# ifcBoard.net
KiCad netlist of a schematic drawn in EAGLE
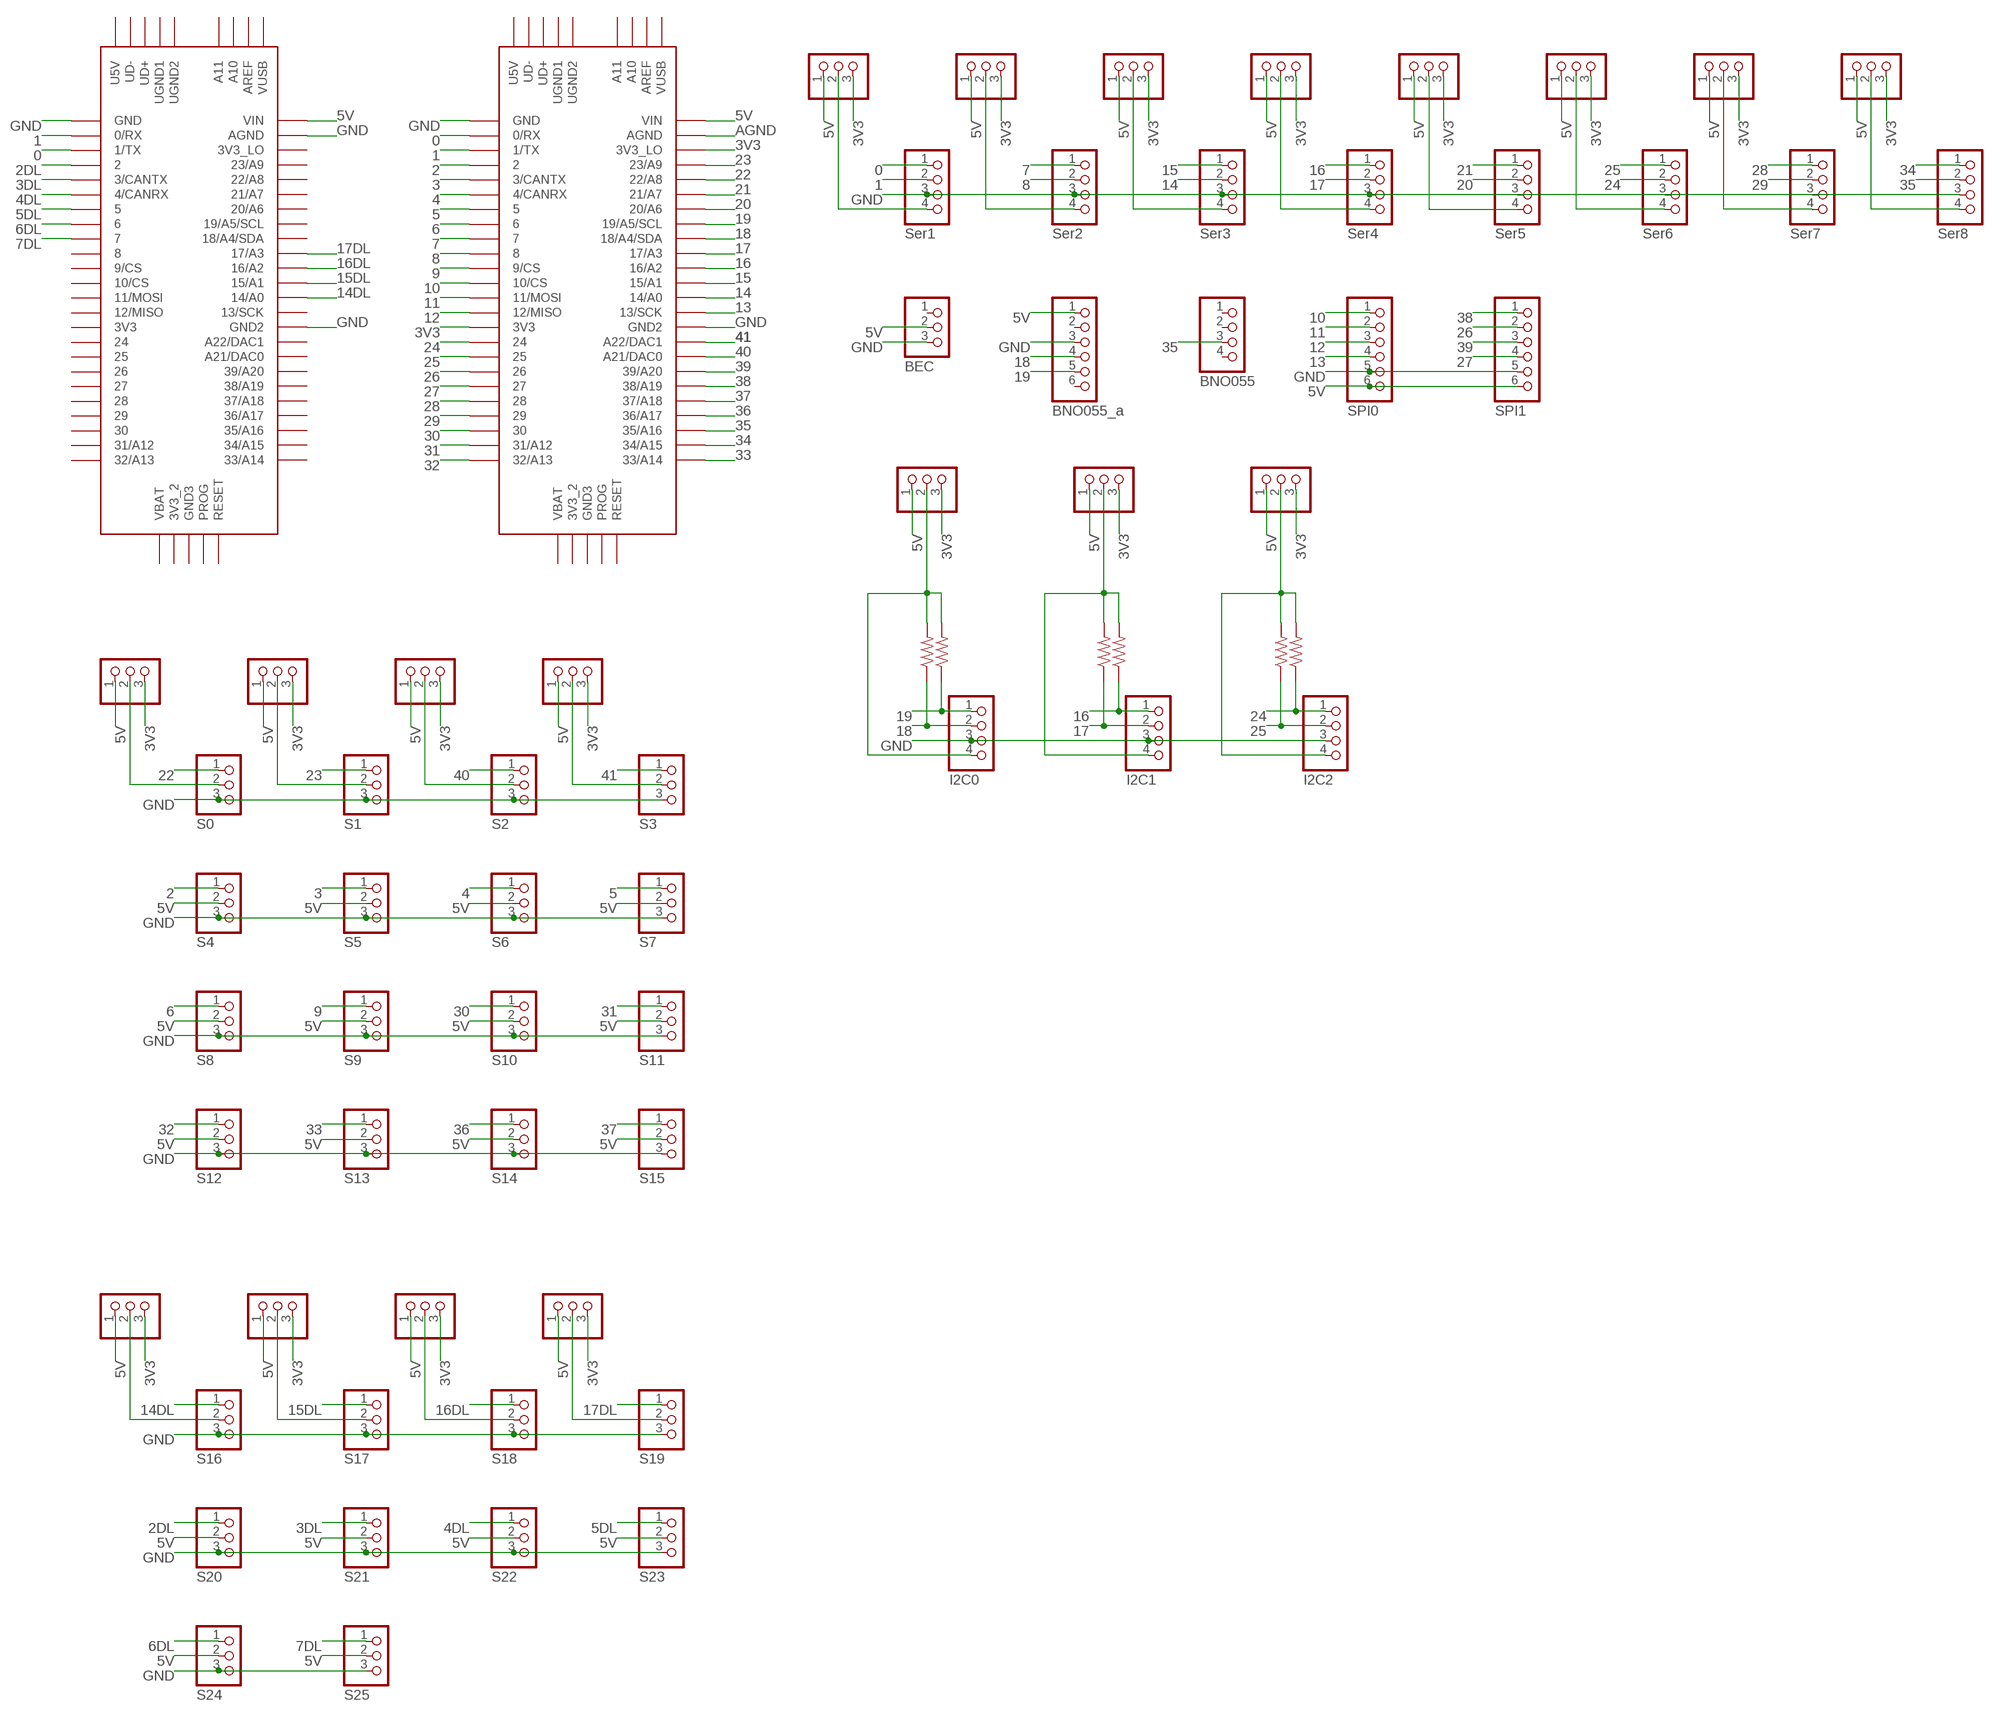
[diagram p0: schematic, sheet 1]

(export (version "E")
  (design (tool "Eeschema 10.0.6"))
  (components
    (comp (ref "JP1")
      (value "BEC")
      (footprint "eagle-import:1X03")
      (libsource (lib "eagle-import") (part "PINHD-1X3"))
    )
    (comp (ref "JP2")
      (value "S0")
      (footprint "eagle-import:1X03")
      (libsource (lib "eagle-import") (part "PINHD-1X3"))
    )
    (comp (ref "JP3")
      (value "S1")
      (footprint "eagle-import:1X03")
      (libsource (lib "eagle-import") (part "PINHD-1X3"))
    )
    (comp (ref "JP4")
      (value "S2")
      (footprint "eagle-import:1X03")
      (libsource (lib "eagle-import") (part "PINHD-1X3"))
    )
    (comp (ref "JP5")
      (value "S3")
      (footprint "eagle-import:1X03")
      (libsource (lib "eagle-import") (part "PINHD-1X3"))
    )
    (comp (ref "JP6")
      (value "S4")
      (footprint "eagle-import:1X03")
      (libsource (lib "eagle-import") (part "PINHD-1X3"))
    )
    (comp (ref "JP7")
      (value "S5")
      (footprint "eagle-import:1X03")
      (libsource (lib "eagle-import") (part "PINHD-1X3"))
    )
    (comp (ref "JP8")
      (value "S6")
      (footprint "eagle-import:1X03")
      (libsource (lib "eagle-import") (part "PINHD-1X3"))
    )
    (comp (ref "JP9")
      (value "S7")
      (footprint "eagle-import:1X03")
      (libsource (lib "eagle-import") (part "PINHD-1X3"))
    )
    (comp (ref "JP10")
      (value "S8")
      (footprint "eagle-import:1X03")
      (libsource (lib "eagle-import") (part "PINHD-1X3"))
    )
    (comp (ref "JP11")
      (value "S9")
      (footprint "eagle-import:1X03")
      (libsource (lib "eagle-import") (part "PINHD-1X3"))
    )
    (comp (ref "JP12")
      (value "S10")
      (footprint "eagle-import:1X03")
      (libsource (lib "eagle-import") (part "PINHD-1X3"))
    )
    (comp (ref "JP13")
      (value "S11")
      (footprint "eagle-import:1X03")
      (libsource (lib "eagle-import") (part "PINHD-1X3"))
    )
    (comp (ref "JP14")
      (value "S12")
      (footprint "eagle-import:1X03")
      (libsource (lib "eagle-import") (part "PINHD-1X3"))
    )
    (comp (ref "JP15")
      (value "S13")
      (footprint "eagle-import:1X03")
      (libsource (lib "eagle-import") (part "PINHD-1X3"))
    )
    (comp (ref "JP16")
      (value "S14")
      (footprint "eagle-import:1X03")
      (libsource (lib "eagle-import") (part "PINHD-1X3"))
    )
    (comp (ref "JP17")
      (value "S15")
      (footprint "eagle-import:1X03")
      (libsource (lib "eagle-import") (part "PINHD-1X3"))
    )
    (comp (ref "JP18")
      (value "Ser6")
      (footprint "eagle-import:1X04")
      (libsource (lib "eagle-import") (part "PINHD-1X4"))
    )
    (comp (ref "JP19")
      (value "S0")
      (footprint "eagle-import:1X03")
      (libsource (lib "eagle-import") (part "PINHD-1X3"))
    )
    (comp (ref "JP20")
      (value "S0")
      (footprint "eagle-import:1X03")
      (libsource (lib "eagle-import") (part "PINHD-1X3"))
    )
    (comp (ref "JP21")
      (value "Ser7")
      (footprint "eagle-import:1X04")
      (libsource (lib "eagle-import") (part "PINHD-1X4"))
    )
    (comp (ref "JP22")
      (value "I2C0")
      (footprint "eagle-import:1X04")
      (libsource (lib "eagle-import") (part "PINHD-1X4"))
    )
    (comp (ref "JP23")
      (value "Ser1")
      (footprint "eagle-import:1X04")
      (libsource (lib "eagle-import") (part "PINHD-1X4"))
    )
    (comp (ref "JP24")
      (value "Ser2")
      (footprint "eagle-import:1X04")
      (libsource (lib "eagle-import") (part "PINHD-1X4"))
    )
    (comp (ref "JP25")
      (value "Ser3")
      (footprint "eagle-import:1X04")
      (libsource (lib "eagle-import") (part "PINHD-1X4"))
    )
    (comp (ref "JP26")
      (value "Ser4")
      (footprint "eagle-import:1X04")
      (libsource (lib "eagle-import") (part "PINHD-1X4"))
    )
    (comp (ref "JP27")
      (value "Ser5")
      (footprint "eagle-import:1X04")
      (libsource (lib "eagle-import") (part "PINHD-1X4"))
    )
    (comp (ref "JP28")
      (value "I2C1")
      (footprint "eagle-import:1X04")
      (libsource (lib "eagle-import") (part "PINHD-1X4"))
    )
    (comp (ref "JP29")
      (value "I2C2")
      (footprint "eagle-import:1X04")
      (libsource (lib "eagle-import") (part "PINHD-1X4"))
    )
    (comp (ref "JP30")
      (value "Ser8")
      (footprint "eagle-import:1X04")
      (libsource (lib "eagle-import") (part "PINHD-1X4"))
    )
    (comp (ref "JP31")
      (value "SPI0")
      (footprint "eagle-import:1X06")
      (libsource (lib "eagle-import") (part "PINHD-1X6"))
    )
    (comp (ref "JP32")
      (value "SPI1")
      (footprint "eagle-import:1X06")
      (libsource (lib "eagle-import") (part "PINHD-1X6"))
    )
    (comp (ref "JP33")
      (value "BNO055_a")
      (footprint "eagle-import:1X06")
      (libsource (lib "eagle-import") (part "PINHD-1X6"))
    )
    (comp (ref "JP34")
      (value "BNO055")
      (footprint "eagle-import:1X04")
      (libsource (lib "eagle-import") (part "PINHD-1X4"))
    )
    (comp (ref "JP35")
      (value "S0")
      (footprint "eagle-import:1X03")
      (libsource (lib "eagle-import") (part "PINHD-1X3"))
    )
    (comp (ref "JP36")
      (value "S0")
      (footprint "eagle-import:1X03")
      (libsource (lib "eagle-import") (part "PINHD-1X3"))
    )
    (comp (ref "JP37")
      (value "S0")
      (footprint "eagle-import:1X03")
      (libsource (lib "eagle-import") (part "PINHD-1X3"))
    )
    (comp (ref "JP38")
      (value "S0")
      (footprint "eagle-import:1X03")
      (libsource (lib "eagle-import") (part "PINHD-1X3"))
    )
    (comp (ref "JP39")
      (value "S0")
      (footprint "eagle-import:1X03")
      (libsource (lib "eagle-import") (part "PINHD-1X3"))
    )
    (comp (ref "JP40")
      (value "S0")
      (footprint "eagle-import:1X03")
      (libsource (lib "eagle-import") (part "PINHD-1X3"))
    )
    (comp (ref "JP41")
      (value "S0")
      (footprint "eagle-import:1X03")
      (libsource (lib "eagle-import") (part "PINHD-1X3"))
    )
    (comp (ref "JP42")
      (value "S0")
      (footprint "eagle-import:1X03")
      (libsource (lib "eagle-import") (part "PINHD-1X3"))
    )
    (comp (ref "JP43")
      (value "S0")
      (footprint "eagle-import:1X03")
      (libsource (lib "eagle-import") (part "PINHD-1X3"))
    )
    (comp (ref "JP44")
      (value "S0")
      (footprint "eagle-import:1X03")
      (libsource (lib "eagle-import") (part "PINHD-1X3"))
    )
    (comp (ref "JP45")
      (value "S0")
      (footprint "eagle-import:1X03")
      (libsource (lib "eagle-import") (part "PINHD-1X3"))
    )
    (comp (ref "JP46")
      (value "S0")
      (footprint "eagle-import:1X03")
      (libsource (lib "eagle-import") (part "PINHD-1X3"))
    )
    (comp (ref "JP47")
      (value "S0")
      (footprint "eagle-import:1X03")
      (libsource (lib "eagle-import") (part "PINHD-1X3"))
    )
    (comp (ref "JP58")
      (value "S16")
      (footprint "eagle-import:1X03")
      (libsource (lib "eagle-import") (part "PINHD-1X3"))
    )
    (comp (ref "JP59")
      (value "S17")
      (footprint "eagle-import:1X03")
      (libsource (lib "eagle-import") (part "PINHD-1X3"))
    )
    (comp (ref "JP60")
      (value "S18")
      (footprint "eagle-import:1X03")
      (libsource (lib "eagle-import") (part "PINHD-1X3"))
    )
    (comp (ref "JP61")
      (value "S19")
      (footprint "eagle-import:1X03")
      (libsource (lib "eagle-import") (part "PINHD-1X3"))
    )
    (comp (ref "JP62")
      (value "S23")
      (footprint "eagle-import:1X03")
      (libsource (lib "eagle-import") (part "PINHD-1X3"))
    )
    (comp (ref "JP63")
      (value "S22")
      (footprint "eagle-import:1X03")
      (libsource (lib "eagle-import") (part "PINHD-1X3"))
    )
    (comp (ref "JP64")
      (value "S0")
      (footprint "eagle-import:1X03")
      (libsource (lib "eagle-import") (part "PINHD-1X3"))
    )
    (comp (ref "JP65")
      (value "S0")
      (footprint "eagle-import:1X03")
      (libsource (lib "eagle-import") (part "PINHD-1X3"))
    )
    (comp (ref "JP66")
      (value "S0")
      (footprint "eagle-import:1X03")
      (libsource (lib "eagle-import") (part "PINHD-1X3"))
    )
    (comp (ref "JP67")
      (value "S0")
      (footprint "eagle-import:1X03")
      (libsource (lib "eagle-import") (part "PINHD-1X3"))
    )
    (comp (ref "JP68")
      (value "S21")
      (footprint "eagle-import:1X03")
      (libsource (lib "eagle-import") (part "PINHD-1X3"))
    )
    (comp (ref "JP69")
      (value "S20")
      (footprint "eagle-import:1X03")
      (libsource (lib "eagle-import") (part "PINHD-1X3"))
    )
    (comp (ref "JP70")
      (value "S24")
      (footprint "eagle-import:1X03")
      (libsource (lib "eagle-import") (part "PINHD-1X3"))
    )
    (comp (ref "JP71")
      (value "S25")
      (footprint "eagle-import:1X03")
      (libsource (lib "eagle-import") (part "PINHD-1X3"))
    )
    (comp (ref "R2")
      (value "R-US_0207/12")
      (footprint "eagle-import:0207_12")
      (libsource (lib "eagle-import") (part "R-US_0207/12"))
    )
    (comp (ref "R3")
      (value "R-US_0207/12")
      (footprint "eagle-import:0207_12")
      (libsource (lib "eagle-import") (part "R-US_0207/12"))
    )
    (comp (ref "R4")
      (value "R-US_0207/12")
      (footprint "eagle-import:0207_12")
      (libsource (lib "eagle-import") (part "R-US_0207/12"))
    )
    (comp (ref "R5")
      (value "R-US_0207/12")
      (footprint "eagle-import:0207_12")
      (libsource (lib "eagle-import") (part "R-US_0207/12"))
    )
    (comp (ref "R6")
      (value "R-US_0207/12")
      (footprint "eagle-import:0207_12")
      (libsource (lib "eagle-import") (part "R-US_0207/12"))
    )
    (comp (ref "R7")
      (value "R-US_0207/12")
      (footprint "eagle-import:0207_12")
      (libsource (lib "eagle-import") (part "R-US_0207/12"))
    )
    (comp (ref "U$1")
      (value "TEENSY_3.5/3.6")
      (footprint "eagle-import:TEENSY_3.5_3.6")
      (libsource (lib "eagle-import") (part "TEENSY_3.5/3.6"))
    )
    (comp (ref "U$2")
      (value "TEENSY_3.5/3.6")
      (footprint "eagle-import:TEENSY_3.5_3.6")
      (libsource (lib "eagle-import") (part "TEENSY_3.5/3.6"))
    )
  )
  (nets
    (net (code "1") (name "/0") (class "Default")
      (node (ref "JP23") (pin "1") (pinfunction "1_1") (pintype "passive"))
      (node (ref "U$1") (pin "0/RX") (pinfunction "0/RX_0/RX") (pintype "bidirectional"))
      (node (ref "U$2") (pin "1/TX") (pinfunction "1/TX_1/TX") (pintype "bidirectional"))
    )
    (net (code "2") (name "/1") (class "Default")
      (node (ref "JP23") (pin "2") (pinfunction "2_2") (pintype "passive"))
      (node (ref "U$1") (pin "1/TX") (pinfunction "1/TX_1/TX") (pintype "bidirectional"))
      (node (ref "U$2") (pin "0/RX") (pinfunction "0/RX_0/RX") (pintype "bidirectional"))
    )
    (net (code "3") (name "/2") (class "Default")
      (node (ref "JP6") (pin "1") (pinfunction "1_1") (pintype "passive"))
      (node (ref "U$1") (pin "2") (pinfunction "2_2") (pintype "bidirectional"))
    )
    (net (code "4") (name "/2DL") (class "Default")
      (node (ref "JP69") (pin "1") (pinfunction "1_1") (pintype "passive"))
      (node (ref "U$2") (pin "2") (pinfunction "2_2") (pintype "bidirectional"))
    )
    (net (code "5") (name "/3") (class "Default")
      (node (ref "JP7") (pin "1") (pinfunction "1_1") (pintype "passive"))
      (node (ref "U$1") (pin "3/CANTX") (pinfunction "3/CANTX_3/CANTX") (pintype "bidirectional"))
    )
    (net (code "6") (name "/3DL") (class "Default")
      (node (ref "JP68") (pin "1") (pinfunction "1_1") (pintype "passive"))
      (node (ref "U$2") (pin "3/CANTX") (pinfunction "3/CANTX_3/CANTX") (pintype "bidirectional"))
    )
    (net (code "7") (name "/3V3") (class "Default")
      (node (ref "JP19") (pin "3") (pinfunction "3_3") (pintype "passive"))
      (node (ref "JP20") (pin "3") (pinfunction "3_3") (pintype "passive"))
      (node (ref "JP35") (pin "3") (pinfunction "3_3") (pintype "passive"))
      (node (ref "JP36") (pin "3") (pinfunction "3_3") (pintype "passive"))
      (node (ref "JP37") (pin "3") (pinfunction "3_3") (pintype "passive"))
      (node (ref "JP38") (pin "3") (pinfunction "3_3") (pintype "passive"))
      (node (ref "JP39") (pin "3") (pinfunction "3_3") (pintype "passive"))
      (node (ref "JP40") (pin "3") (pinfunction "3_3") (pintype "passive"))
      (node (ref "JP41") (pin "3") (pinfunction "3_3") (pintype "passive"))
      (node (ref "JP42") (pin "3") (pinfunction "3_3") (pintype "passive"))
      (node (ref "JP43") (pin "3") (pinfunction "3_3") (pintype "passive"))
      (node (ref "JP44") (pin "3") (pinfunction "3_3") (pintype "passive"))
      (node (ref "JP45") (pin "3") (pinfunction "3_3") (pintype "passive"))
      (node (ref "JP46") (pin "3") (pinfunction "3_3") (pintype "passive"))
      (node (ref "JP47") (pin "3") (pinfunction "3_3") (pintype "passive"))
      (node (ref "JP64") (pin "3") (pinfunction "3_3") (pintype "passive"))
      (node (ref "JP65") (pin "3") (pinfunction "3_3") (pintype "passive"))
      (node (ref "JP66") (pin "3") (pinfunction "3_3") (pintype "passive"))
      (node (ref "JP67") (pin "3") (pinfunction "3_3") (pintype "passive"))
      (node (ref "U$1") (pin "3V3") (pinfunction "3V3_3V3") (pintype "bidirectional"))
      (node (ref "U$1") (pin "3V3_LO") (pinfunction "3V3_LO_3V3_LO") (pintype "bidirectional"))
    )
    (net (code "8") (name "/4") (class "Default")
      (node (ref "JP8") (pin "1") (pinfunction "1_1") (pintype "passive"))
      (node (ref "U$1") (pin "4/CANRX") (pinfunction "4/CANRX_4/CANRX") (pintype "bidirectional"))
    )
    (net (code "9") (name "/4DL") (class "Default")
      (node (ref "JP63") (pin "1") (pinfunction "1_1") (pintype "passive"))
      (node (ref "U$2") (pin "4/CANRX") (pinfunction "4/CANRX_4/CANRX") (pintype "bidirectional"))
    )
    (net (code "10") (name "/5") (class "Default")
      (node (ref "JP9") (pin "1") (pinfunction "1_1") (pintype "passive"))
      (node (ref "U$1") (pin "5") (pinfunction "5_5") (pintype "bidirectional"))
    )
    (net (code "11") (name "/5DL") (class "Default")
      (node (ref "JP62") (pin "1") (pinfunction "1_1") (pintype "passive"))
      (node (ref "U$2") (pin "5") (pinfunction "5_5") (pintype "bidirectional"))
    )
    (net (code "12") (name "/5V") (class "Default")
      (node (ref "JP1") (pin "2") (pinfunction "2_2") (pintype "passive"))
      (node (ref "JP10") (pin "2") (pinfunction "2_2") (pintype "passive"))
      (node (ref "JP11") (pin "2") (pinfunction "2_2") (pintype "passive"))
      (node (ref "JP12") (pin "2") (pinfunction "2_2") (pintype "passive"))
      (node (ref "JP13") (pin "2") (pinfunction "2_2") (pintype "passive"))
      (node (ref "JP14") (pin "2") (pinfunction "2_2") (pintype "passive"))
      (node (ref "JP15") (pin "2") (pinfunction "2_2") (pintype "passive"))
      (node (ref "JP16") (pin "2") (pinfunction "2_2") (pintype "passive"))
      (node (ref "JP17") (pin "2") (pinfunction "2_2") (pintype "passive"))
      (node (ref "JP19") (pin "1") (pinfunction "1_1") (pintype "passive"))
      (node (ref "JP20") (pin "1") (pinfunction "1_1") (pintype "passive"))
      (node (ref "JP22") (pin "4") (pinfunction "4_4") (pintype "passive"))
      (node (ref "JP31") (pin "6") (pinfunction "6_6") (pintype "passive"))
      (node (ref "JP32") (pin "6") (pinfunction "6_6") (pintype "passive"))
      (node (ref "JP33") (pin "1") (pinfunction "1_1") (pintype "passive"))
      (node (ref "JP35") (pin "1") (pinfunction "1_1") (pintype "passive"))
      (node (ref "JP36") (pin "1") (pinfunction "1_1") (pintype "passive"))
      (node (ref "JP37") (pin "1") (pinfunction "1_1") (pintype "passive"))
      (node (ref "JP38") (pin "1") (pinfunction "1_1") (pintype "passive"))
      (node (ref "JP39") (pin "1") (pinfunction "1_1") (pintype "passive"))
      (node (ref "JP40") (pin "1") (pinfunction "1_1") (pintype "passive"))
      (node (ref "JP40") (pin "2") (pinfunction "2_2") (pintype "passive"))
      (node (ref "JP41") (pin "1") (pinfunction "1_1") (pintype "passive"))
      (node (ref "JP42") (pin "1") (pinfunction "1_1") (pintype "passive"))
      (node (ref "JP43") (pin "1") (pinfunction "1_1") (pintype "passive"))
      (node (ref "JP44") (pin "1") (pinfunction "1_1") (pintype "passive"))
      (node (ref "JP45") (pin "1") (pinfunction "1_1") (pintype "passive"))
      (node (ref "JP46") (pin "1") (pinfunction "1_1") (pintype "passive"))
      (node (ref "JP47") (pin "1") (pinfunction "1_1") (pintype "passive"))
      (node (ref "JP6") (pin "2") (pinfunction "2_2") (pintype "passive"))
      (node (ref "JP62") (pin "2") (pinfunction "2_2") (pintype "passive"))
      (node (ref "JP63") (pin "2") (pinfunction "2_2") (pintype "passive"))
      (node (ref "JP64") (pin "1") (pinfunction "1_1") (pintype "passive"))
      (node (ref "JP65") (pin "1") (pinfunction "1_1") (pintype "passive"))
      (node (ref "JP66") (pin "1") (pinfunction "1_1") (pintype "passive"))
      (node (ref "JP67") (pin "1") (pinfunction "1_1") (pintype "passive"))
      (node (ref "JP68") (pin "2") (pinfunction "2_2") (pintype "passive"))
      (node (ref "JP69") (pin "2") (pinfunction "2_2") (pintype "passive"))
      (node (ref "JP7") (pin "2") (pinfunction "2_2") (pintype "passive"))
      (node (ref "JP70") (pin "2") (pinfunction "2_2") (pintype "passive"))
      (node (ref "JP71") (pin "2") (pinfunction "2_2") (pintype "passive"))
      (node (ref "JP8") (pin "2") (pinfunction "2_2") (pintype "passive"))
      (node (ref "JP9") (pin "2") (pinfunction "2_2") (pintype "passive"))
      (node (ref "R2") (pin "2") (pinfunction "2_2") (pintype "passive"))
      (node (ref "R3") (pin "2") (pinfunction "2_2") (pintype "passive"))
      (node (ref "U$1") (pin "VIN") (pinfunction "VIN_VIN") (pintype "bidirectional"))
      (node (ref "U$2") (pin "VIN") (pinfunction "VIN_VIN") (pintype "bidirectional"))
    )
    (net (code "13") (name "/6") (class "Default")
      (node (ref "JP10") (pin "1") (pinfunction "1_1") (pintype "passive"))
      (node (ref "U$1") (pin "6") (pinfunction "6_6") (pintype "bidirectional"))
    )
    (net (code "14") (name "/6DL") (class "Default")
      (node (ref "JP70") (pin "1") (pinfunction "1_1") (pintype "passive"))
      (node (ref "U$2") (pin "6") (pinfunction "6_6") (pintype "bidirectional"))
    )
    (net (code "15") (name "/7") (class "Default")
      (node (ref "JP24") (pin "1") (pinfunction "1_1") (pintype "passive"))
      (node (ref "U$1") (pin "7") (pinfunction "7_7") (pintype "bidirectional"))
    )
    (net (code "16") (name "/7DL") (class "Default")
      (node (ref "JP71") (pin "1") (pinfunction "1_1") (pintype "passive"))
      (node (ref "U$2") (pin "7") (pinfunction "7_7") (pintype "bidirectional"))
    )
    (net (code "17") (name "/8") (class "Default")
      (node (ref "JP24") (pin "2") (pinfunction "2_2") (pintype "passive"))
      (node (ref "U$1") (pin "8") (pinfunction "8_8") (pintype "bidirectional"))
    )
    (net (code "18") (name "/9") (class "Default")
      (node (ref "JP11") (pin "1") (pinfunction "1_1") (pintype "passive"))
      (node (ref "U$1") (pin "9/CS") (pinfunction "9/CS_9/CS") (pintype "bidirectional"))
    )
    (net (code "19") (name "/10") (class "Default")
      (node (ref "JP31") (pin "1") (pinfunction "1_1") (pintype "passive"))
      (node (ref "U$1") (pin "10/CS") (pinfunction "10/CS_10/CS") (pintype "bidirectional"))
    )
    (net (code "20") (name "/11") (class "Default")
      (node (ref "JP31") (pin "2") (pinfunction "2_2") (pintype "passive"))
      (node (ref "U$1") (pin "11/MOSI") (pinfunction "11/MOSI_11/MOSI") (pintype "bidirectional"))
    )
    (net (code "21") (name "/12") (class "Default")
      (node (ref "JP31") (pin "3") (pinfunction "3_3") (pintype "passive"))
      (node (ref "U$1") (pin "12/MISO") (pinfunction "12/MISO_12/MISO") (pintype "bidirectional"))
    )
    (net (code "22") (name "/13") (class "Default")
      (node (ref "JP31") (pin "4") (pinfunction "4_4") (pintype "passive"))
      (node (ref "U$1") (pin "13/SCK") (pinfunction "13/SCK_13/SCK") (pintype "bidirectional"))
    )
    (net (code "23") (name "/14") (class "Default")
      (node (ref "JP25") (pin "2") (pinfunction "2_2") (pintype "passive"))
      (node (ref "U$1") (pin "14/A0") (pinfunction "14/A0_14/A0") (pintype "bidirectional"))
    )
    (net (code "24") (name "/14DL") (class "Default")
      (node (ref "JP58") (pin "1") (pinfunction "1_1") (pintype "passive"))
      (node (ref "U$2") (pin "14/A0") (pinfunction "14/A0_14/A0") (pintype "bidirectional"))
    )
    (net (code "25") (name "/15") (class "Default")
      (node (ref "JP25") (pin "1") (pinfunction "1_1") (pintype "passive"))
      (node (ref "U$1") (pin "15/A1") (pinfunction "15/A1_15/A1") (pintype "bidirectional"))
    )
    (net (code "26") (name "/15DL") (class "Default")
      (node (ref "JP59") (pin "1") (pinfunction "1_1") (pintype "passive"))
      (node (ref "U$2") (pin "15/A1") (pinfunction "15/A1_15/A1") (pintype "bidirectional"))
    )
    (net (code "27") (name "/16") (class "Default")
      (node (ref "JP26") (pin "1") (pinfunction "1_1") (pintype "passive"))
      (node (ref "JP28") (pin "1") (pinfunction "1_1") (pintype "passive"))
      (node (ref "R6") (pin "1") (pinfunction "1_1") (pintype "passive"))
      (node (ref "U$1") (pin "16/A2") (pinfunction "16/A2_16/A2") (pintype "bidirectional"))
    )
    (net (code "28") (name "/16DL") (class "Default")
      (node (ref "JP60") (pin "1") (pinfunction "1_1") (pintype "passive"))
      (node (ref "U$2") (pin "16/A2") (pinfunction "16/A2_16/A2") (pintype "bidirectional"))
    )
    (net (code "29") (name "/17") (class "Default")
      (node (ref "JP26") (pin "2") (pinfunction "2_2") (pintype "passive"))
      (node (ref "JP28") (pin "2") (pinfunction "2_2") (pintype "passive"))
      (node (ref "R4") (pin "1") (pinfunction "1_1") (pintype "passive"))
      (node (ref "U$1") (pin "17/A3") (pinfunction "17/A3_17/A3") (pintype "bidirectional"))
    )
    (net (code "30") (name "/17DL") (class "Default")
      (node (ref "JP61") (pin "1") (pinfunction "1_1") (pintype "passive"))
      (node (ref "U$2") (pin "17/A3") (pinfunction "17/A3_17/A3") (pintype "bidirectional"))
    )
    (net (code "31") (name "/18") (class "Default")
      (node (ref "JP22") (pin "2") (pinfunction "2_2") (pintype "passive"))
      (node (ref "JP33") (pin "4") (pinfunction "4_4") (pintype "passive"))
      (node (ref "R2") (pin "1") (pinfunction "1_1") (pintype "passive"))
      (node (ref "U$1") (pin "18/A4/SDA") (pinfunction "18/A4/SDA_18/A4/SDA") (pintype "bidirectional"))
    )
    (net (code "32") (name "/19") (class "Default")
      (node (ref "JP22") (pin "1") (pinfunction "1_1") (pintype "passive"))
      (node (ref "JP33") (pin "5") (pinfunction "5_5") (pintype "passive"))
      (node (ref "R3") (pin "1") (pinfunction "1_1") (pintype "passive"))
      (node (ref "U$1") (pin "19/A5/SCL") (pinfunction "19/A5/SCL_19/A5/SCL") (pintype "bidirectional"))
    )
    (net (code "33") (name "/20") (class "Default")
      (node (ref "JP27") (pin "2") (pinfunction "2_2") (pintype "passive"))
      (node (ref "U$1") (pin "20/A6") (pinfunction "20/A6_20/A6") (pintype "bidirectional"))
    )
    (net (code "34") (name "/21") (class "Default")
      (node (ref "JP27") (pin "1") (pinfunction "1_1") (pintype "passive"))
      (node (ref "U$1") (pin "21/A7") (pinfunction "21/A7_21/A7") (pintype "bidirectional"))
    )
    (net (code "35") (name "/22") (class "Default")
      (node (ref "JP2") (pin "1") (pinfunction "1_1") (pintype "passive"))
      (node (ref "U$1") (pin "22/A8") (pinfunction "22/A8_22/A8") (pintype "bidirectional"))
    )
    (net (code "36") (name "/23") (class "Default")
      (node (ref "JP3") (pin "1") (pinfunction "1_1") (pintype "passive"))
      (node (ref "U$1") (pin "23/A9") (pinfunction "23/A9_23/A9") (pintype "bidirectional"))
    )
    (net (code "37") (name "/24") (class "Default")
      (node (ref "JP18") (pin "2") (pinfunction "2_2") (pintype "passive"))
      (node (ref "JP29") (pin "1") (pinfunction "1_1") (pintype "passive"))
      (node (ref "R5") (pin "1") (pinfunction "1_1") (pintype "passive"))
      (node (ref "U$1") (pin "24") (pinfunction "24_24") (pintype "bidirectional"))
    )
    (net (code "38") (name "/25") (class "Default")
      (node (ref "JP18") (pin "1") (pinfunction "1_1") (pintype "passive"))
      (node (ref "JP29") (pin "2") (pinfunction "2_2") (pintype "passive"))
      (node (ref "R7") (pin "1") (pinfunction "1_1") (pintype "passive"))
      (node (ref "U$1") (pin "25") (pinfunction "25_25") (pintype "bidirectional"))
    )
    (net (code "39") (name "/26") (class "Default")
      (node (ref "JP32") (pin "2") (pinfunction "2_2") (pintype "passive"))
      (node (ref "U$1") (pin "26") (pinfunction "26_26") (pintype "bidirectional"))
    )
    (net (code "40") (name "/27") (class "Default")
      (node (ref "JP32") (pin "4") (pinfunction "4_4") (pintype "passive"))
      (node (ref "U$1") (pin "27") (pinfunction "27_27") (pintype "bidirectional"))
    )
    (net (code "41") (name "/28") (class "Default")
      (node (ref "JP21") (pin "1") (pinfunction "1_1") (pintype "passive"))
      (node (ref "U$1") (pin "28") (pinfunction "28_28") (pintype "bidirectional"))
    )
    (net (code "42") (name "/29") (class "Default")
      (node (ref "JP21") (pin "2") (pinfunction "2_2") (pintype "passive"))
      (node (ref "U$1") (pin "29") (pinfunction "29_29") (pintype "bidirectional"))
    )
    (net (code "43") (name "/30") (class "Default")
      (node (ref "JP12") (pin "1") (pinfunction "1_1") (pintype "passive"))
      (node (ref "U$1") (pin "30") (pinfunction "30_30") (pintype "bidirectional"))
    )
    (net (code "44") (name "/31") (class "Default")
      (node (ref "JP13") (pin "1") (pinfunction "1_1") (pintype "passive"))
      (node (ref "U$1") (pin "31/A12") (pinfunction "31/A12_31/A12") (pintype "bidirectional"))
    )
    (net (code "45") (name "/32") (class "Default")
      (node (ref "JP14") (pin "1") (pinfunction "1_1") (pintype "passive"))
      (node (ref "U$1") (pin "32/A13") (pinfunction "32/A13_32/A13") (pintype "bidirectional"))
    )
    (net (code "46") (name "/33") (class "Default")
      (node (ref "JP15") (pin "1") (pinfunction "1_1") (pintype "passive"))
      (node (ref "U$1") (pin "33/A14") (pinfunction "33/A14_33/A14") (pintype "bidirectional"))
    )
    (net (code "47") (name "/34") (class "Default")
      (node (ref "JP30") (pin "1") (pinfunction "1_1") (pintype "passive"))
      (node (ref "U$1") (pin "34/A15") (pinfunction "34/A15_34/A15") (pintype "bidirectional"))
    )
    (net (code "48") (name "/35") (class "Default")
      (node (ref "JP30") (pin "2") (pinfunction "2_2") (pintype "passive"))
      (node (ref "JP34") (pin "3") (pinfunction "3_3") (pintype "passive"))
      (node (ref "U$1") (pin "35/A16") (pinfunction "35/A16_35/A16") (pintype "bidirectional"))
    )
    (net (code "49") (name "/36") (class "Default")
      (node (ref "JP16") (pin "1") (pinfunction "1_1") (pintype "passive"))
      (node (ref "U$1") (pin "36/A17") (pinfunction "36/A17_36/A17") (pintype "bidirectional"))
    )
    (net (code "50") (name "/37") (class "Default")
      (node (ref "JP17") (pin "1") (pinfunction "1_1") (pintype "passive"))
      (node (ref "U$1") (pin "37/A18") (pinfunction "37/A18_37/A18") (pintype "bidirectional"))
    )
    (net (code "51") (name "/38") (class "Default")
      (node (ref "JP32") (pin "1") (pinfunction "1_1") (pintype "passive"))
      (node (ref "U$1") (pin "38/A19") (pinfunction "38/A19_38/A19") (pintype "bidirectional"))
    )
    (net (code "52") (name "/39") (class "Default")
      (node (ref "JP32") (pin "3") (pinfunction "3_3") (pintype "passive"))
      (node (ref "U$1") (pin "39/A20") (pinfunction "39/A20_39/A20") (pintype "bidirectional"))
    )
    (net (code "53") (name "/40") (class "Default")
      (node (ref "JP4") (pin "1") (pinfunction "1_1") (pintype "passive"))
      (node (ref "U$1") (pin "21/DAC0") (pinfunction "A21/DAC0_21/DAC0") (pintype "bidirectional"))
    )
    (net (code "54") (name "/41") (class "Default")
      (node (ref "JP5") (pin "1") (pinfunction "1_1") (pintype "passive"))
      (node (ref "U$1") (pin "A22/DAC1") (pinfunction "A22/DAC1_A22/DAC1") (pintype "bidirectional"))
    )
    (net (code "55") (name "/AGND") (class "Default")
      (node (ref "U$1") (pin "AGND") (pinfunction "AGND_AGND") (pintype "bidirectional"))
    )
    (net (code "56") (name "/GND") (class "Default")
      (node (ref "JP1") (pin "3") (pinfunction "3_3") (pintype "passive"))
      (node (ref "JP10") (pin "3") (pinfunction "3_3") (pintype "passive"))
      (node (ref "JP11") (pin "3") (pinfunction "3_3") (pintype "passive"))
      (node (ref "JP12") (pin "3") (pinfunction "3_3") (pintype "passive"))
      (node (ref "JP13") (pin "3") (pinfunction "3_3") (pintype "passive"))
      (node (ref "JP14") (pin "3") (pinfunction "3_3") (pintype "passive"))
      (node (ref "JP15") (pin "3") (pinfunction "3_3") (pintype "passive"))
      (node (ref "JP16") (pin "3") (pinfunction "3_3") (pintype "passive"))
      (node (ref "JP17") (pin "3") (pinfunction "3_3") (pintype "passive"))
      (node (ref "JP18") (pin "3") (pinfunction "3_3") (pintype "passive"))
      (node (ref "JP2") (pin "3") (pinfunction "3_3") (pintype "passive"))
      (node (ref "JP21") (pin "3") (pinfunction "3_3") (pintype "passive"))
      (node (ref "JP22") (pin "3") (pinfunction "3_3") (pintype "passive"))
      (node (ref "JP23") (pin "3") (pinfunction "3_3") (pintype "passive"))
      (node (ref "JP24") (pin "3") (pinfunction "3_3") (pintype "passive"))
      (node (ref "JP25") (pin "3") (pinfunction "3_3") (pintype "passive"))
      (node (ref "JP26") (pin "3") (pinfunction "3_3") (pintype "passive"))
      (node (ref "JP27") (pin "3") (pinfunction "3_3") (pintype "passive"))
      (node (ref "JP28") (pin "3") (pinfunction "3_3") (pintype "passive"))
      (node (ref "JP29") (pin "3") (pinfunction "3_3") (pintype "passive"))
      (node (ref "JP3") (pin "3") (pinfunction "3_3") (pintype "passive"))
      (node (ref "JP30") (pin "3") (pinfunction "3_3") (pintype "passive"))
      (node (ref "JP31") (pin "5") (pinfunction "5_5") (pintype "passive"))
      (node (ref "JP32") (pin "5") (pinfunction "5_5") (pintype "passive"))
      (node (ref "JP33") (pin "3") (pinfunction "3_3") (pintype "passive"))
      (node (ref "JP4") (pin "3") (pinfunction "3_3") (pintype "passive"))
      (node (ref "JP5") (pin "3") (pinfunction "3_3") (pintype "passive"))
      (node (ref "JP58") (pin "3") (pinfunction "3_3") (pintype "passive"))
      (node (ref "JP59") (pin "3") (pinfunction "3_3") (pintype "passive"))
      (node (ref "JP6") (pin "3") (pinfunction "3_3") (pintype "passive"))
      (node (ref "JP60") (pin "3") (pinfunction "3_3") (pintype "passive"))
      (node (ref "JP61") (pin "3") (pinfunction "3_3") (pintype "passive"))
      (node (ref "JP62") (pin "3") (pinfunction "3_3") (pintype "passive"))
      (node (ref "JP63") (pin "3") (pinfunction "3_3") (pintype "passive"))
      (node (ref "JP68") (pin "3") (pinfunction "3_3") (pintype "passive"))
      (node (ref "JP69") (pin "3") (pinfunction "3_3") (pintype "passive"))
      (node (ref "JP7") (pin "3") (pinfunction "3_3") (pintype "passive"))
      (node (ref "JP70") (pin "3") (pinfunction "3_3") (pintype "passive"))
      (node (ref "JP71") (pin "3") (pinfunction "3_3") (pintype "passive"))
      (node (ref "JP8") (pin "3") (pinfunction "3_3") (pintype "passive"))
      (node (ref "JP9") (pin "3") (pinfunction "3_3") (pintype "passive"))
      (node (ref "U$1") (pin "GND") (pinfunction "GND_GND") (pintype "bidirectional"))
      (node (ref "U$1") (pin "GND2") (pinfunction "GND2_GND2") (pintype "bidirectional"))
      (node (ref "U$2") (pin "AGND") (pinfunction "AGND_AGND") (pintype "bidirectional"))
      (node (ref "U$2") (pin "GND") (pinfunction "GND_GND") (pintype "bidirectional"))
      (node (ref "U$2") (pin "GND2") (pinfunction "GND2_GND2") (pintype "bidirectional"))
    )
    (net (code "57") (name "Net-(JP2-Pad2)") (class "Default")
      (node (ref "JP2") (pin "2") (pinfunction "2_2") (pintype "passive"))
      (node (ref "JP42") (pin "2") (pinfunction "2_2") (pintype "passive"))
    )
    (net (code "58") (name "Net-(JP3-Pad2)") (class "Default")
      (node (ref "JP3") (pin "2") (pinfunction "2_2") (pintype "passive"))
      (node (ref "JP45") (pin "2") (pinfunction "2_2") (pintype "passive"))
    )
    (net (code "59") (name "Net-(JP4-Pad2)") (class "Default")
      (node (ref "JP4") (pin "2") (pinfunction "2_2") (pintype "passive"))
      (node (ref "JP46") (pin "2") (pinfunction "2_2") (pintype "passive"))
    )
    (net (code "60") (name "Net-(JP18-Pad4)") (class "Default")
      (node (ref "JP18") (pin "4") (pinfunction "4_4") (pintype "passive"))
      (node (ref "JP38") (pin "2") (pinfunction "2_2") (pintype "passive"))
    )
    (net (code "61") (name "Net-(JP19-Pad2)") (class "Default")
      (node (ref "JP19") (pin "2") (pinfunction "2_2") (pintype "passive"))
      (node (ref "JP23") (pin "4") (pinfunction "4_4") (pintype "passive"))
    )
    (net (code "62") (name "Net-(JP20-Pad2)") (class "Default")
      (node (ref "JP20") (pin "2") (pinfunction "2_2") (pintype "passive"))
      (node (ref "JP24") (pin "4") (pinfunction "4_4") (pintype "passive"))
    )
    (net (code "63") (name "Net-(JP21-Pad4)") (class "Default")
      (node (ref "JP21") (pin "4") (pinfunction "4_4") (pintype "passive"))
      (node (ref "JP39") (pin "2") (pinfunction "2_2") (pintype "passive"))
    )
    (net (code "64") (name "Net-(JP25-Pad4)") (class "Default")
      (node (ref "JP25") (pin "4") (pinfunction "4_4") (pintype "passive"))
      (node (ref "JP35") (pin "2") (pinfunction "2_2") (pintype "passive"))
    )
    (net (code "65") (name "Net-(JP26-Pad4)") (class "Default")
      (node (ref "JP26") (pin "4") (pinfunction "4_4") (pintype "passive"))
      (node (ref "JP36") (pin "2") (pinfunction "2_2") (pintype "passive"))
    )
    (net (code "66") (name "Net-(JP27-Pad4)") (class "Default")
      (node (ref "JP27") (pin "4") (pinfunction "4_4") (pintype "passive"))
      (node (ref "JP37") (pin "2") (pinfunction "2_2") (pintype "passive"))
    )
    (net (code "67") (name "Net-(JP28-Pad4)") (class "Default")
      (node (ref "JP28") (pin "4") (pinfunction "4_4") (pintype "passive"))
      (node (ref "JP43") (pin "2") (pinfunction "2_2") (pintype "passive"))
      (node (ref "R4") (pin "2") (pinfunction "2_2") (pintype "passive"))
      (node (ref "R6") (pin "2") (pinfunction "2_2") (pintype "passive"))
    )
    (net (code "68") (name "Net-(JP29-Pad4)") (class "Default")
      (node (ref "JP29") (pin "4") (pinfunction "4_4") (pintype "passive"))
      (node (ref "JP44") (pin "2") (pinfunction "2_2") (pintype "passive"))
      (node (ref "R5") (pin "2") (pinfunction "2_2") (pintype "passive"))
      (node (ref "R7") (pin "2") (pinfunction "2_2") (pintype "passive"))
    )
    (net (code "69") (name "Net-(JP30-Pad4)") (class "Default")
      (node (ref "JP30") (pin "4") (pinfunction "4_4") (pintype "passive"))
      (node (ref "JP41") (pin "2") (pinfunction "2_2") (pintype "passive"))
    )
    (net (code "70") (name "Net-(JP47-Pad2)") (class "Default")
      (node (ref "JP47") (pin "2") (pinfunction "2_2") (pintype "passive"))
      (node (ref "JP5") (pin "2") (pinfunction "2_2") (pintype "passive"))
    )
    (net (code "71") (name "Net-(JP58-Pad2)") (class "Default")
      (node (ref "JP58") (pin "2") (pinfunction "2_2") (pintype "passive"))
      (node (ref "JP64") (pin "2") (pinfunction "2_2") (pintype "passive"))
    )
    (net (code "72") (name "Net-(JP59-Pad2)") (class "Default")
      (node (ref "JP59") (pin "2") (pinfunction "2_2") (pintype "passive"))
      (node (ref "JP65") (pin "2") (pinfunction "2_2") (pintype "passive"))
    )
    (net (code "73") (name "Net-(JP60-Pad2)") (class "Default")
      (node (ref "JP60") (pin "2") (pinfunction "2_2") (pintype "passive"))
      (node (ref "JP66") (pin "2") (pinfunction "2_2") (pintype "passive"))
    )
    (net (code "74") (name "Net-(JP61-Pad2)") (class "Default")
      (node (ref "JP61") (pin "2") (pinfunction "2_2") (pintype "passive"))
      (node (ref "JP67") (pin "2") (pinfunction "2_2") (pintype "passive"))
    )
    (net (code "75") (name "unconnected-(JP1-Pad1)") (class "Default")
      (node (ref "JP1") (pin "1") (pinfunction "1_1") (pintype "passive"))
    )
    (net (code "76") (name "unconnected-(JP33-Pad2)") (class "Default")
      (node (ref "JP33") (pin "2") (pinfunction "2_2") (pintype "passive"))
    )
    (net (code "77") (name "unconnected-(JP33-Pad6)") (class "Default")
      (node (ref "JP33") (pin "6") (pinfunction "6_6") (pintype "passive"))
    )
    (net (code "78") (name "unconnected-(JP34-Pad1)") (class "Default")
      (node (ref "JP34") (pin "1") (pinfunction "1_1") (pintype "passive"))
    )
    (net (code "79") (name "unconnected-(JP34-Pad2)") (class "Default")
      (node (ref "JP34") (pin "2") (pinfunction "2_2") (pintype "passive"))
    )
    (net (code "80") (name "unconnected-(JP34-Pad4)") (class "Default")
      (node (ref "JP34") (pin "4") (pinfunction "4_4") (pintype "passive"))
    )
    (net (code "81") (name "unconnected-(U$1-Pad3V3_2)") (class "Default")
      (node (ref "U$1") (pin "3V3_2") (pinfunction "3V3_2_3V3_2") (pintype "bidirectional"))
    )
    (net (code "82") (name "unconnected-(U$1-PadA10)") (class "Default")
      (node (ref "U$1") (pin "A10") (pinfunction "A10_A10") (pintype "bidirectional"))
    )
    (net (code "83") (name "unconnected-(U$1-PadA11)") (class "Default")
      (node (ref "U$1") (pin "A11") (pinfunction "A11_A11") (pintype "bidirectional"))
    )
    (net (code "84") (name "unconnected-(U$1-PadAREF)") (class "Default")
      (node (ref "U$1") (pin "AREF") (pinfunction "AREF_AREF") (pintype "bidirectional"))
    )
    (net (code "85") (name "unconnected-(U$1-PadGND3)") (class "Default")
      (node (ref "U$1") (pin "GND3") (pinfunction "GND3_GND3") (pintype "bidirectional"))
    )
    (net (code "86") (name "unconnected-(U$1-PadPROG)") (class "Default")
      (node (ref "U$1") (pin "PROG") (pinfunction "PROG_PROG") (pintype "bidirectional"))
    )
    (net (code "87") (name "unconnected-(U$1-PadRESET)") (class "Default")
      (node (ref "U$1") (pin "RESET") (pinfunction "RESET_RESET") (pintype "bidirectional"))
    )
    (net (code "88") (name "unconnected-(U$1-PadU5V)") (class "Default")
      (node (ref "U$1") (pin "U5V") (pinfunction "U5V_U5V") (pintype "bidirectional"))
    )
    (net (code "89") (name "unconnected-(U$1-PadUD+)") (class "Default")
      (node (ref "U$1") (pin "UD+") (pinfunction "UD+_UD+") (pintype "bidirectional"))
    )
    (net (code "90") (name "unconnected-(U$1-PadUD-)") (class "Default")
      (node (ref "U$1") (pin "UD-") (pinfunction "UD-_UD-") (pintype "bidirectional"))
    )
    (net (code "91") (name "unconnected-(U$1-PadUGND1)") (class "Default")
      (node (ref "U$1") (pin "UGND1") (pinfunction "UGND1_UGND1") (pintype "bidirectional"))
    )
    (net (code "92") (name "unconnected-(U$1-PadUGND2)") (class "Default")
      (node (ref "U$1") (pin "UGND2") (pinfunction "UGND2_UGND2") (pintype "bidirectional"))
    )
    (net (code "93") (name "unconnected-(U$1-PadVBAT)") (class "Default")
      (node (ref "U$1") (pin "VBAT") (pinfunction "VBAT_VBAT") (pintype "bidirectional"))
    )
    (net (code "94") (name "unconnected-(U$1-PadVUSB)") (class "Default")
      (node (ref "U$1") (pin "VUSB") (pinfunction "VUSB_VUSB") (pintype "bidirectional"))
    )
    (net (code "95") (name "unconnected-(U$2-A21{slash}DAC0-Pad21{slash}DAC0)") (class "Default")
      (node (ref "U$2") (pin "21/DAC0") (pinfunction "A21/DAC0_21/DAC0") (pintype "bidirectional"))
    )
    (net (code "96") (name "unconnected-(U$2-Pad3V3)") (class "Default")
      (node (ref "U$2") (pin "3V3") (pinfunction "3V3_3V3") (pintype "bidirectional"))
    )
    (net (code "97") (name "unconnected-(U$2-Pad3V3_2)") (class "Default")
      (node (ref "U$2") (pin "3V3_2") (pinfunction "3V3_2_3V3_2") (pintype "bidirectional"))
    )
    (net (code "98") (name "unconnected-(U$2-Pad3V3_LO)") (class "Default")
      (node (ref "U$2") (pin "3V3_LO") (pinfunction "3V3_LO_3V3_LO") (pintype "bidirectional"))
    )
    (net (code "99") (name "unconnected-(U$2-Pad8)") (class "Default")
      (node (ref "U$2") (pin "8") (pinfunction "8_8") (pintype "bidirectional"))
    )
    (net (code "100") (name "unconnected-(U$2-Pad9{slash}CS)") (class "Default")
      (node (ref "U$2") (pin "9/CS") (pinfunction "9/CS_9/CS") (pintype "bidirectional"))
    )
    (net (code "101") (name "unconnected-(U$2-Pad10{slash}CS)") (class "Default")
      (node (ref "U$2") (pin "10/CS") (pinfunction "10/CS_10/CS") (pintype "bidirectional"))
    )
    (net (code "102") (name "unconnected-(U$2-Pad11{slash}MOSI)") (class "Default")
      (node (ref "U$2") (pin "11/MOSI") (pinfunction "11/MOSI_11/MOSI") (pintype "bidirectional"))
    )
    (net (code "103") (name "unconnected-(U$2-Pad12{slash}MISO)") (class "Default")
      (node (ref "U$2") (pin "12/MISO") (pinfunction "12/MISO_12/MISO") (pintype "bidirectional"))
    )
    (net (code "104") (name "unconnected-(U$2-Pad13{slash}SCK)") (class "Default")
      (node (ref "U$2") (pin "13/SCK") (pinfunction "13/SCK_13/SCK") (pintype "bidirectional"))
    )
    (net (code "105") (name "unconnected-(U$2-Pad18{slash}A4{slash}SDA)") (class "Default")
      (node (ref "U$2") (pin "18/A4/SDA") (pinfunction "18/A4/SDA_18/A4/SDA") (pintype "bidirectional"))
    )
    (net (code "106") (name "unconnected-(U$2-Pad19{slash}A5{slash}SCL)") (class "Default")
      (node (ref "U$2") (pin "19/A5/SCL") (pinfunction "19/A5/SCL_19/A5/SCL") (pintype "bidirectional"))
    )
    (net (code "107") (name "unconnected-(U$2-Pad20{slash}A6)") (class "Default")
      (node (ref "U$2") (pin "20/A6") (pinfunction "20/A6_20/A6") (pintype "bidirectional"))
    )
    (net (code "108") (name "unconnected-(U$2-Pad21{slash}A7)") (class "Default")
      (node (ref "U$2") (pin "21/A7") (pinfunction "21/A7_21/A7") (pintype "bidirectional"))
    )
    (net (code "109") (name "unconnected-(U$2-Pad22{slash}A8)") (class "Default")
      (node (ref "U$2") (pin "22/A8") (pinfunction "22/A8_22/A8") (pintype "bidirectional"))
    )
    (net (code "110") (name "unconnected-(U$2-Pad23{slash}A9)") (class "Default")
      (node (ref "U$2") (pin "23/A9") (pinfunction "23/A9_23/A9") (pintype "bidirectional"))
    )
    (net (code "111") (name "unconnected-(U$2-Pad24)") (class "Default")
      (node (ref "U$2") (pin "24") (pinfunction "24_24") (pintype "bidirectional"))
    )
    (net (code "112") (name "unconnected-(U$2-Pad25)") (class "Default")
      (node (ref "U$2") (pin "25") (pinfunction "25_25") (pintype "bidirectional"))
    )
    (net (code "113") (name "unconnected-(U$2-Pad26)") (class "Default")
      (node (ref "U$2") (pin "26") (pinfunction "26_26") (pintype "bidirectional"))
    )
    (net (code "114") (name "unconnected-(U$2-Pad27)") (class "Default")
      (node (ref "U$2") (pin "27") (pinfunction "27_27") (pintype "bidirectional"))
    )
    (net (code "115") (name "unconnected-(U$2-Pad28)") (class "Default")
      (node (ref "U$2") (pin "28") (pinfunction "28_28") (pintype "bidirectional"))
    )
    (net (code "116") (name "unconnected-(U$2-Pad29)") (class "Default")
      (node (ref "U$2") (pin "29") (pinfunction "29_29") (pintype "bidirectional"))
    )
    (net (code "117") (name "unconnected-(U$2-Pad30)") (class "Default")
      (node (ref "U$2") (pin "30") (pinfunction "30_30") (pintype "bidirectional"))
    )
    (net (code "118") (name "unconnected-(U$2-Pad31{slash}A12)") (class "Default")
      (node (ref "U$2") (pin "31/A12") (pinfunction "31/A12_31/A12") (pintype "bidirectional"))
    )
    (net (code "119") (name "unconnected-(U$2-Pad32{slash}A13)") (class "Default")
      (node (ref "U$2") (pin "32/A13") (pinfunction "32/A13_32/A13") (pintype "bidirectional"))
    )
    (net (code "120") (name "unconnected-(U$2-Pad33{slash}A14)") (class "Default")
      (node (ref "U$2") (pin "33/A14") (pinfunction "33/A14_33/A14") (pintype "bidirectional"))
    )
    (net (code "121") (name "unconnected-(U$2-Pad34{slash}A15)") (class "Default")
      (node (ref "U$2") (pin "34/A15") (pinfunction "34/A15_34/A15") (pintype "bidirectional"))
    )
    (net (code "122") (name "unconnected-(U$2-Pad35{slash}A16)") (class "Default")
      (node (ref "U$2") (pin "35/A16") (pinfunction "35/A16_35/A16") (pintype "bidirectional"))
    )
    (net (code "123") (name "unconnected-(U$2-Pad36{slash}A17)") (class "Default")
      (node (ref "U$2") (pin "36/A17") (pinfunction "36/A17_36/A17") (pintype "bidirectional"))
    )
    (net (code "124") (name "unconnected-(U$2-Pad37{slash}A18)") (class "Default")
      (node (ref "U$2") (pin "37/A18") (pinfunction "37/A18_37/A18") (pintype "bidirectional"))
    )
    (net (code "125") (name "unconnected-(U$2-Pad38{slash}A19)") (class "Default")
      (node (ref "U$2") (pin "38/A19") (pinfunction "38/A19_38/A19") (pintype "bidirectional"))
    )
    (net (code "126") (name "unconnected-(U$2-Pad39{slash}A20)") (class "Default")
      (node (ref "U$2") (pin "39/A20") (pinfunction "39/A20_39/A20") (pintype "bidirectional"))
    )
    (net (code "127") (name "unconnected-(U$2-PadA10)") (class "Default")
      (node (ref "U$2") (pin "A10") (pinfunction "A10_A10") (pintype "bidirectional"))
    )
    (net (code "128") (name "unconnected-(U$2-PadA11)") (class "Default")
      (node (ref "U$2") (pin "A11") (pinfunction "A11_A11") (pintype "bidirectional"))
    )
    (net (code "129") (name "unconnected-(U$2-PadA22{slash}DAC1)") (class "Default")
      (node (ref "U$2") (pin "A22/DAC1") (pinfunction "A22/DAC1_A22/DAC1") (pintype "bidirectional"))
    )
    (net (code "130") (name "unconnected-(U$2-PadAREF)") (class "Default")
      (node (ref "U$2") (pin "AREF") (pinfunction "AREF_AREF") (pintype "bidirectional"))
    )
    (net (code "131") (name "unconnected-(U$2-PadGND3)") (class "Default")
      (node (ref "U$2") (pin "GND3") (pinfunction "GND3_GND3") (pintype "bidirectional"))
    )
    (net (code "132") (name "unconnected-(U$2-PadPROG)") (class "Default")
      (node (ref "U$2") (pin "PROG") (pinfunction "PROG_PROG") (pintype "bidirectional"))
    )
    (net (code "133") (name "unconnected-(U$2-PadRESET)") (class "Default")
      (node (ref "U$2") (pin "RESET") (pinfunction "RESET_RESET") (pintype "bidirectional"))
    )
    (net (code "134") (name "unconnected-(U$2-PadU5V)") (class "Default")
      (node (ref "U$2") (pin "U5V") (pinfunction "U5V_U5V") (pintype "bidirectional"))
    )
    (net (code "135") (name "unconnected-(U$2-PadUD+)") (class "Default")
      (node (ref "U$2") (pin "UD+") (pinfunction "UD+_UD+") (pintype "bidirectional"))
    )
    (net (code "136") (name "unconnected-(U$2-PadUD-)") (class "Default")
      (node (ref "U$2") (pin "UD-") (pinfunction "UD-_UD-") (pintype "bidirectional"))
    )
    (net (code "137") (name "unconnected-(U$2-PadUGND1)") (class "Default")
      (node (ref "U$2") (pin "UGND1") (pinfunction "UGND1_UGND1") (pintype "bidirectional"))
    )
    (net (code "138") (name "unconnected-(U$2-PadUGND2)") (class "Default")
      (node (ref "U$2") (pin "UGND2") (pinfunction "UGND2_UGND2") (pintype "bidirectional"))
    )
    (net (code "139") (name "unconnected-(U$2-PadVBAT)") (class "Default")
      (node (ref "U$2") (pin "VBAT") (pinfunction "VBAT_VBAT") (pintype "bidirectional"))
    )
    (net (code "140") (name "unconnected-(U$2-PadVUSB)") (class "Default")
      (node (ref "U$2") (pin "VUSB") (pinfunction "VUSB_VUSB") (pintype "bidirectional"))
    )
  )
)
